# Photoresistor_ADC.net
KiCad netlist of a schematic drawn in EAGLE
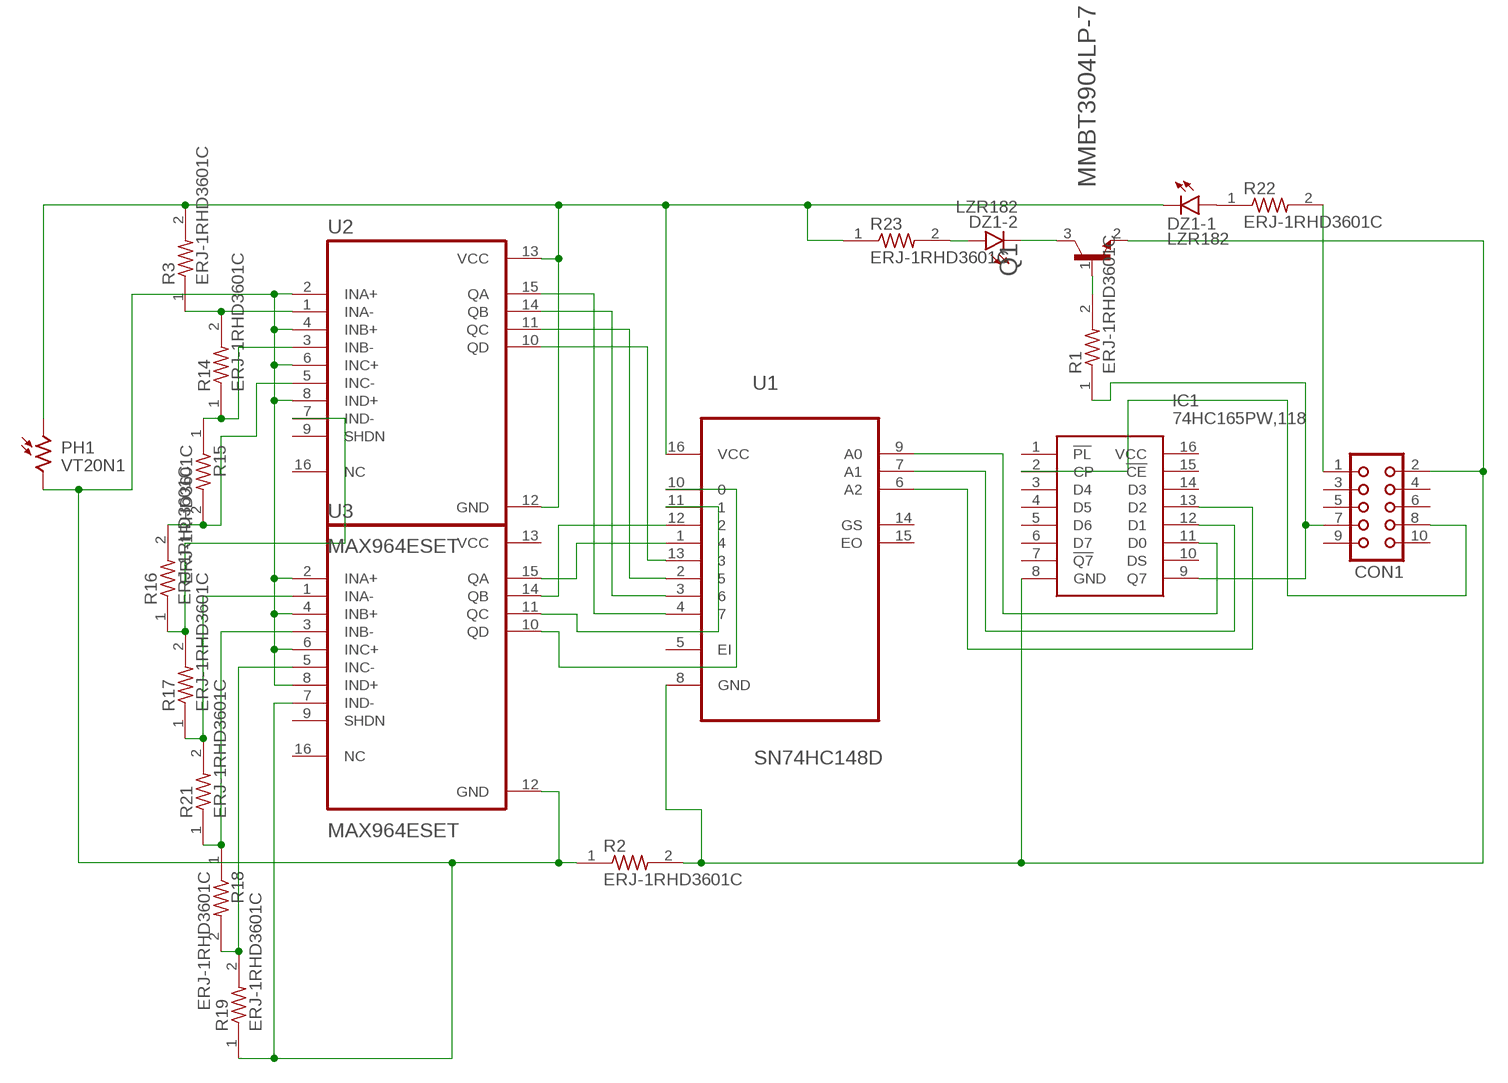
[diagram p0: schematic, sheet 1]

(export (version "E")
  (design (tool "Eeschema 10.0.6"))
  (components
    (comp (ref "CON1")
      (value "CON10L")
      (footprint "eagle-import:CON10L")
      (libsource (lib "eagle-import") (part "CON10L"))
    )
    (comp (ref "DZ1")
      (value "LZR182")
      (footprint "eagle-import:LZR182")
      (libsource (lib "eagle-import") (part "LZR182"))
    )
    (comp (ref "IC1")
      (value "74HC165PW,118")
      (footprint "eagle-import:SOP65P640X110-16N")
      (fields (field (name "MOUSER_PART_NUMBER") "771-74HC165PW-T"))
      (libsource (lib "eagle-import") (part "74HC165PW,118"))
    )
    (comp (ref "PH1")
      (value "VT20N1")
      (footprint "eagle-import:TO46-VT200")
      (libsource (lib "eagle-import") (part "VT20N1"))
    )
    (comp (ref "Q1")
      (value "MMBT3904LP-7")
      (footprint "eagle-import:DFN101X61X53-3N")
      (fields (field (name "DIGI-KEY_PART_NUMBER") "MMBT3904LP-7DICT-ND") (field (name "MF") "Diodes Inc."))
      (libsource (lib "eagle-import") (part "MMBT3904LP-7"))
    )
    (comp (ref "R1")
      (value "ERJ-1RHD3601C")
      (footprint "eagle-import:RESC0603X26N")
      (fields (field (name "MF") "Panasonic"))
      (libsource (lib "eagle-import") (part "ERJ-1RHD3601C"))
    )
    (comp (ref "R2")
      (value "ERJ-1RHD3601C")
      (footprint "eagle-import:RESC0603X26N")
      (fields (field (name "MF") "Panasonic"))
      (libsource (lib "eagle-import") (part "ERJ-1RHD3601C"))
    )
    (comp (ref "R3")
      (value "ERJ-1RHD3601C")
      (footprint "eagle-import:RESC0603X26N")
      (fields (field (name "MF") "Panasonic"))
      (libsource (lib "eagle-import") (part "ERJ-1RHD3601C"))
    )
    (comp (ref "R14")
      (value "ERJ-1RHD3601C")
      (footprint "eagle-import:RESC0603X26N")
      (fields (field (name "MF") "Panasonic"))
      (libsource (lib "eagle-import") (part "ERJ-1RHD3601C"))
    )
    (comp (ref "R15")
      (value "ERJ-1RHD3601C")
      (footprint "eagle-import:RESC0603X26N")
      (fields (field (name "MF") "Panasonic"))
      (libsource (lib "eagle-import") (part "ERJ-1RHD3601C"))
    )
    (comp (ref "R16")
      (value "ERJ-1RHD3601C")
      (footprint "eagle-import:RESC0603X26N")
      (fields (field (name "MF") "Panasonic"))
      (libsource (lib "eagle-import") (part "ERJ-1RHD3601C"))
    )
    (comp (ref "R17")
      (value "ERJ-1RHD3601C")
      (footprint "eagle-import:RESC0603X26N")
      (fields (field (name "MF") "Panasonic"))
      (libsource (lib "eagle-import") (part "ERJ-1RHD3601C"))
    )
    (comp (ref "R18")
      (value "ERJ-1RHD3601C")
      (footprint "eagle-import:RESC0603X26N")
      (fields (field (name "MF") "Panasonic"))
      (libsource (lib "eagle-import") (part "ERJ-1RHD3601C"))
    )
    (comp (ref "R19")
      (value "ERJ-1RHD3601C")
      (footprint "eagle-import:RESC0603X26N")
      (fields (field (name "MF") "Panasonic"))
      (libsource (lib "eagle-import") (part "ERJ-1RHD3601C"))
    )
    (comp (ref "R21")
      (value "ERJ-1RHD3601C")
      (footprint "eagle-import:RESC0603X26N")
      (fields (field (name "MF") "Panasonic"))
      (libsource (lib "eagle-import") (part "ERJ-1RHD3601C"))
    )
    (comp (ref "R22")
      (value "ERJ-1RHD3601C")
      (footprint "eagle-import:RESC0603X26N")
      (fields (field (name "MF") "Panasonic"))
      (libsource (lib "eagle-import") (part "ERJ-1RHD3601C"))
    )
    (comp (ref "R23")
      (value "ERJ-1RHD3601C")
      (footprint "eagle-import:RESC0603X26N")
      (fields (field (name "MF") "Panasonic"))
      (libsource (lib "eagle-import") (part "ERJ-1RHD3601C"))
    )
    (comp (ref "U1")
      (value "SN74HC148D")
      (footprint "eagle-import:SOIC127P600X175-16N")
      (fields (field (name "MF") "Texas Instruments"))
      (libsource (lib "eagle-import") (part "SN74HC148D"))
    )
    (comp (ref "U2")
      (value "MAX964ESET")
      (footprint "eagle-import:SOIC127P600X175-16N")
      (fields (field (name "MF") "Maxim Integrated") (field (name "MP") "MAX964ESE+"))
      (libsource (lib "eagle-import") (part "MAX964ESET"))
    )
    (comp (ref "U3")
      (value "MAX964ESET")
      (footprint "eagle-import:SOIC127P600X175-16N")
      (fields (field (name "MF") "Maxim Integrated") (field (name "MP") "MAX964ESE+"))
      (libsource (lib "eagle-import") (part "MAX964ESET"))
    )
  )
  (nets
    (net (code "1") (name "/VCC") (class "Default")
      (node (ref "U3") (pin "13") (pinfunction "VCC_13") (pintype "power_in"))
    )
    (net (code "2") (name "Net-(CON1-Pad1)") (class "Default")
      (node (ref "CON1") (pin "1") (pinfunction "1_1") (pintype "passive"))
      (node (ref "R22") (pin "2") (pinfunction "2_2") (pintype "passive"))
    )
    (net (code "3") (name "Net-(DZ1A-A)") (class "Default")
      (node (ref "DZ1") (pin "A1") (pinfunction "A_A1") (pintype "passive"))
      (node (ref "R22") (pin "1") (pinfunction "1_1") (pintype "passive"))
    )
    (net (code "4") (name "Net-(DZ1A-C)") (class "Default")
      (node (ref "DZ1") (pin "K1") (pinfunction "C_K1") (pintype "passive"))
      (node (ref "PH1") (pin "1") (pinfunction "1_1") (pintype "passive"))
      (node (ref "R23") (pin "1") (pinfunction "1_1") (pintype "passive"))
      (node (ref "R3") (pin "2") (pinfunction "2_2") (pintype "passive"))
      (node (ref "U1") (pin "16") (pinfunction "VCC_16") (pintype "power_in"))
      (node (ref "U2") (pin "12") (pinfunction "GND_12") (pintype "power_in"))
      (node (ref "U2") (pin "13") (pinfunction "VCC_13") (pintype "power_in"))
    )
    (net (code "5") (name "Net-(DZ1B-A)") (class "Default")
      (node (ref "DZ1") (pin "A2") (pinfunction "A_A2") (pintype "passive"))
      (node (ref "R23") (pin "2") (pinfunction "2_2") (pintype "passive"))
    )
    (net (code "6") (name "Net-(DZ1B-C)") (class "Default")
      (node (ref "DZ1") (pin "K2") (pinfunction "C_K2") (pintype "passive"))
      (node (ref "Q1") (pin "3") (pinfunction "C_3") (pintype "passive"))
    )
    (net (code "7") (name "Net-(IC1-CP)") (class "Default")
      (node (ref "CON1") (pin "8") (pinfunction "8_8") (pintype "passive"))
      (node (ref "IC1") (pin "2") (pinfunction "CP_2") (pintype "bidirectional"))
    )
    (net (code "8") (name "Net-(IC1-D0)") (class "Default")
      (node (ref "IC1") (pin "11") (pinfunction "D0_11") (pintype "bidirectional"))
      (node (ref "U1") (pin "9") (pinfunction "A0_9") (pintype "output"))
    )
    (net (code "9") (name "Net-(IC1-D1)") (class "Default")
      (node (ref "IC1") (pin "12") (pinfunction "D1_12") (pintype "bidirectional"))
      (node (ref "U1") (pin "7") (pinfunction "A1_7") (pintype "output"))
    )
    (net (code "10") (name "Net-(IC1-D2)") (class "Default")
      (node (ref "IC1") (pin "13") (pinfunction "D2_13") (pintype "bidirectional"))
      (node (ref "U1") (pin "6") (pinfunction "A2_6") (pintype "output"))
    )
    (net (code "11") (name "Net-(IC1-GND)") (class "Default")
      (node (ref "CON1") (pin "2") (pinfunction "2_2") (pintype "passive"))
      (node (ref "IC1") (pin "8") (pinfunction "GND_8") (pintype "bidirectional"))
      (node (ref "Q1") (pin "2") (pinfunction "E_2") (pintype "passive"))
      (node (ref "R2") (pin "2") (pinfunction "2_2") (pintype "passive"))
      (node (ref "U1") (pin "8") (pinfunction "GND_8") (pintype "passive"))
    )
    (net (code "12") (name "Net-(IC1-Q7)") (class "Default")
      (node (ref "CON1") (pin "7") (pinfunction "7_7") (pintype "passive"))
      (node (ref "IC1") (pin "9") (pinfunction "Q7_9") (pintype "bidirectional"))
      (node (ref "R1") (pin "1") (pinfunction "1_1") (pintype "passive"))
    )
    (net (code "13") (name "Net-(Q1-B)") (class "Default")
      (node (ref "Q1") (pin "1") (pinfunction "B_1") (pintype "passive"))
      (node (ref "R1") (pin "2") (pinfunction "2_2") (pintype "passive"))
    )
    (net (code "14") (name "Net-(U1-0)") (class "Default")
      (node (ref "U1") (pin "10") (pinfunction "0_10") (pintype "input"))
      (node (ref "U3") (pin "10") (pinfunction "QD_10") (pintype "output"))
    )
    (net (code "15") (name "Net-(U1-1)") (class "Default")
      (node (ref "U1") (pin "11") (pinfunction "1_11") (pintype "input"))
      (node (ref "U3") (pin "11") (pinfunction "QC_11") (pintype "output"))
    )
    (net (code "16") (name "Net-(U1-2)") (class "Default")
      (node (ref "U1") (pin "12") (pinfunction "2_12") (pintype "input"))
      (node (ref "U3") (pin "14") (pinfunction "QB_14") (pintype "output"))
    )
    (net (code "17") (name "Net-(U1-3)") (class "Default")
      (node (ref "U1") (pin "13") (pinfunction "3_13") (pintype "input"))
      (node (ref "U2") (pin "10") (pinfunction "QD_10") (pintype "output"))
    )
    (net (code "18") (name "Net-(U1-4)") (class "Default")
      (node (ref "U1") (pin "1") (pinfunction "4_1") (pintype "input"))
      (node (ref "U3") (pin "15") (pinfunction "QA_15") (pintype "output"))
    )
    (net (code "19") (name "Net-(U1-5)") (class "Default")
      (node (ref "U1") (pin "2") (pinfunction "5_2") (pintype "input"))
      (node (ref "U2") (pin "11") (pinfunction "QC_11") (pintype "output"))
    )
    (net (code "20") (name "Net-(U1-6)") (class "Default")
      (node (ref "U1") (pin "3") (pinfunction "6_3") (pintype "input"))
      (node (ref "U2") (pin "14") (pinfunction "QB_14") (pintype "output"))
    )
    (net (code "21") (name "Net-(U1-7)") (class "Default")
      (node (ref "U1") (pin "4") (pinfunction "7_4") (pintype "input"))
      (node (ref "U2") (pin "15") (pinfunction "QA_15") (pintype "output"))
    )
    (net (code "22") (name "Net-(U2-INA+)") (class "Default")
      (node (ref "PH1") (pin "2") (pinfunction "2_2") (pintype "passive"))
      (node (ref "R19") (pin "1") (pinfunction "1_1") (pintype "passive"))
      (node (ref "R2") (pin "1") (pinfunction "1_1") (pintype "passive"))
      (node (ref "U2") (pin "2") (pinfunction "INA+_2") (pintype "input"))
      (node (ref "U2") (pin "4") (pinfunction "INB+_4") (pintype "input"))
      (node (ref "U2") (pin "6") (pinfunction "INC+_6") (pintype "input"))
      (node (ref "U2") (pin "8") (pinfunction "IND+_8") (pintype "input"))
      (node (ref "U3") (pin "12") (pinfunction "GND_12") (pintype "power_in"))
      (node (ref "U3") (pin "2") (pinfunction "INA+_2") (pintype "input"))
      (node (ref "U3") (pin "4") (pinfunction "INB+_4") (pintype "input"))
      (node (ref "U3") (pin "6") (pinfunction "INC+_6") (pintype "input"))
      (node (ref "U3") (pin "7") (pinfunction "IND-_7") (pintype "input"))
      (node (ref "U3") (pin "8") (pinfunction "IND+_8") (pintype "input"))
    )
    (net (code "23") (name "Net-(U2-INA-)") (class "Default")
      (node (ref "R14") (pin "2") (pinfunction "2_2") (pintype "passive"))
      (node (ref "R3") (pin "1") (pinfunction "1_1") (pintype "passive"))
      (node (ref "U2") (pin "1") (pinfunction "INA-_1") (pintype "input"))
    )
    (net (code "24") (name "Net-(U2-INB-)") (class "Default")
      (node (ref "R14") (pin "1") (pinfunction "1_1") (pintype "passive"))
      (node (ref "R15") (pin "1") (pinfunction "1_1") (pintype "passive"))
      (node (ref "U2") (pin "3") (pinfunction "INB-_3") (pintype "input"))
    )
    (net (code "25") (name "Net-(U2-INC-)") (class "Default")
      (node (ref "R15") (pin "2") (pinfunction "2_2") (pintype "passive"))
      (node (ref "R16") (pin "2") (pinfunction "2_2") (pintype "passive"))
      (node (ref "U2") (pin "5") (pinfunction "INC-_5") (pintype "input"))
    )
    (net (code "26") (name "Net-(U2-IND-)") (class "Default")
      (node (ref "R16") (pin "1") (pinfunction "1_1") (pintype "passive"))
      (node (ref "R17") (pin "2") (pinfunction "2_2") (pintype "passive"))
      (node (ref "U2") (pin "7") (pinfunction "IND-_7") (pintype "input"))
    )
    (net (code "27") (name "Net-(U3-INA-)") (class "Default")
      (node (ref "R17") (pin "1") (pinfunction "1_1") (pintype "passive"))
      (node (ref "R21") (pin "2") (pinfunction "2_2") (pintype "passive"))
      (node (ref "U3") (pin "1") (pinfunction "INA-_1") (pintype "input"))
    )
    (net (code "28") (name "Net-(U3-INB-)") (class "Default")
      (node (ref "R18") (pin "1") (pinfunction "1_1") (pintype "passive"))
      (node (ref "R21") (pin "1") (pinfunction "1_1") (pintype "passive"))
      (node (ref "U3") (pin "3") (pinfunction "INB-_3") (pintype "input"))
    )
    (net (code "29") (name "Net-(U3-INC-)") (class "Default")
      (node (ref "R18") (pin "2") (pinfunction "2_2") (pintype "passive"))
      (node (ref "R19") (pin "2") (pinfunction "2_2") (pintype "passive"))
      (node (ref "U3") (pin "5") (pinfunction "INC-_5") (pintype "input"))
    )
    (net (code "30") (name "unconnected-(CON1-Pad3)") (class "Default")
      (node (ref "CON1") (pin "3") (pinfunction "3_3") (pintype "passive"))
    )
    (net (code "31") (name "unconnected-(CON1-Pad4)") (class "Default")
      (node (ref "CON1") (pin "4") (pinfunction "4_4") (pintype "passive"))
    )
    (net (code "32") (name "unconnected-(CON1-Pad5)") (class "Default")
      (node (ref "CON1") (pin "5") (pinfunction "5_5") (pintype "passive"))
    )
    (net (code "33") (name "unconnected-(CON1-Pad6)") (class "Default")
      (node (ref "CON1") (pin "6") (pinfunction "6_6") (pintype "passive"))
    )
    (net (code "34") (name "unconnected-(CON1-Pad9)") (class "Default")
      (node (ref "CON1") (pin "9") (pinfunction "9_9") (pintype "passive"))
    )
    (net (code "35") (name "unconnected-(CON1-Pad10)") (class "Default")
      (node (ref "CON1") (pin "10") (pinfunction "10_10") (pintype "passive"))
    )
    (net (code "36") (name "unconnected-(IC1-D3-Pad14)") (class "Default")
      (node (ref "IC1") (pin "14") (pinfunction "D3_14") (pintype "bidirectional"))
    )
    (net (code "37") (name "unconnected-(IC1-D4-Pad3)") (class "Default")
      (node (ref "IC1") (pin "3") (pinfunction "D4_3") (pintype "bidirectional"))
    )
    (net (code "38") (name "unconnected-(IC1-D5-Pad4)") (class "Default")
      (node (ref "IC1") (pin "4") (pinfunction "D5_4") (pintype "bidirectional"))
    )
    (net (code "39") (name "unconnected-(IC1-D6-Pad5)") (class "Default")
      (node (ref "IC1") (pin "5") (pinfunction "D6_5") (pintype "bidirectional"))
    )
    (net (code "40") (name "unconnected-(IC1-D7-Pad6)") (class "Default")
      (node (ref "IC1") (pin "6") (pinfunction "D7_6") (pintype "bidirectional"))
    )
    (net (code "41") (name "unconnected-(IC1-DS-Pad10)") (class "Default")
      (node (ref "IC1") (pin "10") (pinfunction "DS_10") (pintype "bidirectional"))
    )
    (net (code "42") (name "unconnected-(IC1-VCC-Pad16)") (class "Default")
      (node (ref "IC1") (pin "16") (pinfunction "VCC_16") (pintype "bidirectional"))
    )
    (net (code "43") (name "unconnected-(IC1-~{CE}-Pad15)") (class "Default")
      (node (ref "IC1") (pin "15") (pinfunction "~{CE}_15") (pintype "bidirectional"))
    )
    (net (code "44") (name "unconnected-(IC1-~{PL}-Pad1)") (class "Default")
      (node (ref "IC1") (pin "1") (pinfunction "~{PL}_1") (pintype "bidirectional"))
    )
    (net (code "45") (name "unconnected-(IC1-~{Q7}-Pad7)") (class "Default")
      (node (ref "IC1") (pin "7") (pinfunction "~{Q7}_7") (pintype "bidirectional"))
    )
    (net (code "46") (name "unconnected-(U1-EI-Pad5)") (class "Default")
      (node (ref "U1") (pin "5") (pinfunction "EI_5") (pintype "input"))
    )
    (net (code "47") (name "unconnected-(U1-EO-Pad15)") (class "Default")
      (node (ref "U1") (pin "15") (pinfunction "EO_15") (pintype "output"))
    )
    (net (code "48") (name "unconnected-(U1-GS-Pad14)") (class "Default")
      (node (ref "U1") (pin "14") (pinfunction "GS_14") (pintype "output"))
    )
    (net (code "49") (name "unconnected-(U2-NC-Pad16)") (class "Default")
      (node (ref "U2") (pin "16") (pinfunction "NC_16") (pintype "bidirectional"))
    )
    (net (code "50") (name "unconnected-(U2-SHDN-Pad9)") (class "Default")
      (node (ref "U2") (pin "9") (pinfunction "SHDN_9") (pintype "input"))
    )
    (net (code "51") (name "unconnected-(U3-NC-Pad16)") (class "Default")
      (node (ref "U3") (pin "16") (pinfunction "NC_16") (pintype "bidirectional"))
    )
    (net (code "52") (name "unconnected-(U3-SHDN-Pad9)") (class "Default")
      (node (ref "U3") (pin "9") (pinfunction "SHDN_9") (pintype "input"))
    )
  )
)
